# SCK_URBAN_BOARD_2_2.net
KiCad netlist of a schematic drawn in EAGLE
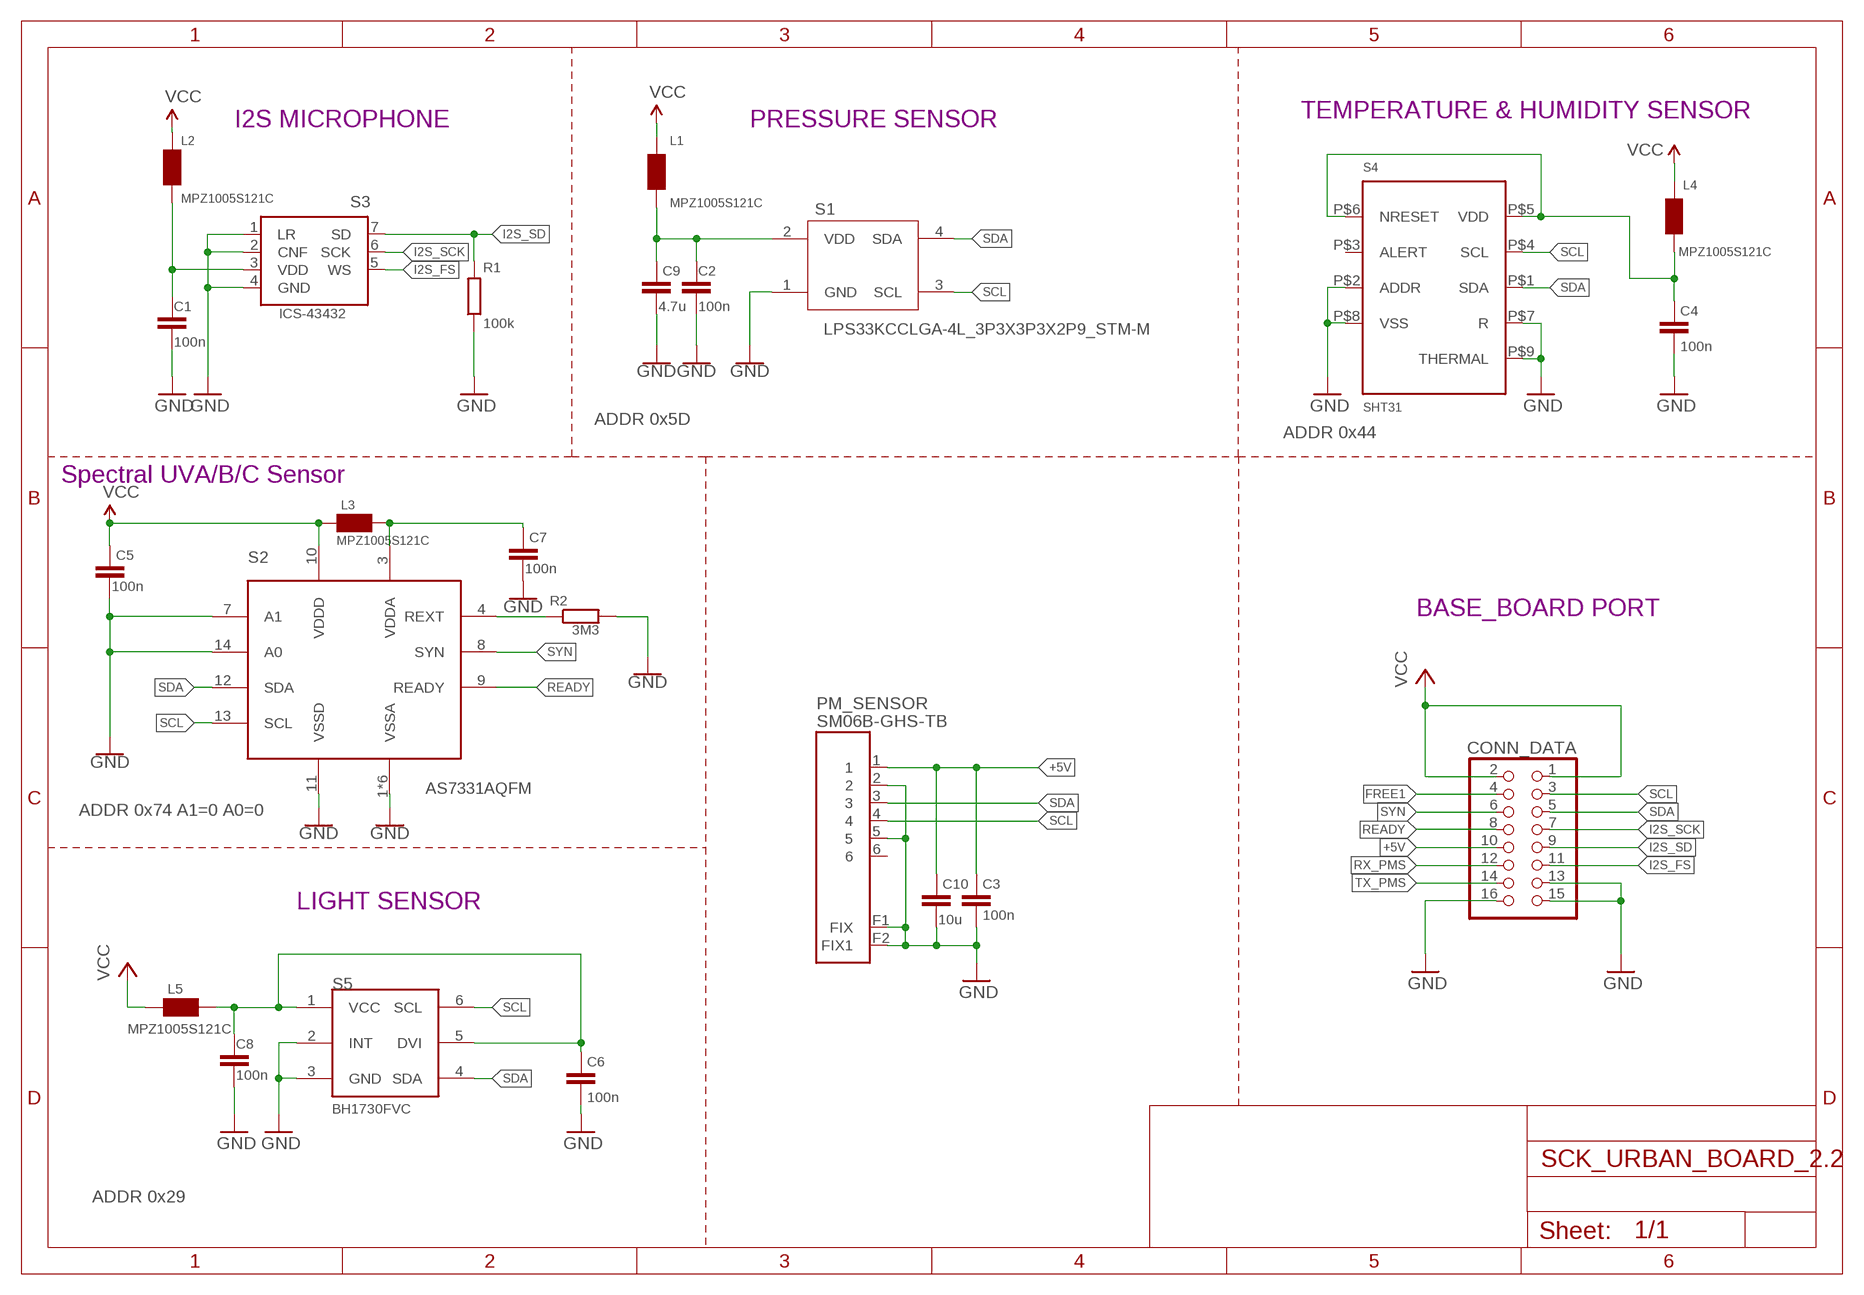
[diagram p0: schematic, sheet 1]

(export (version "E")
  (design (tool "Eeschema 10.0.6"))
  (components
    (comp (ref "C1")
      (value "100n")
      (footprint "eagle-import:C0402")
      (libsource (lib "eagle-import") (part "C-EUC0402"))
    )
    (comp (ref "C2")
      (value "100n")
      (footprint "eagle-import:C0402")
      (libsource (lib "eagle-import") (part "C-EUC0402"))
    )
    (comp (ref "C3")
      (value "100n")
      (footprint "eagle-import:C0402")
      (libsource (lib "eagle-import") (part "C-EUC0402"))
    )
    (comp (ref "C4")
      (value "100n")
      (footprint "eagle-import:C0402")
      (libsource (lib "eagle-import") (part "C-EUC0402"))
    )
    (comp (ref "C5")
      (value "100n")
      (footprint "eagle-import:C0402")
      (libsource (lib "eagle-import") (part "C-EUC0402"))
    )
    (comp (ref "C6")
      (value "100n")
      (footprint "eagle-import:C0402")
      (libsource (lib "eagle-import") (part "C-EUC0402"))
    )
    (comp (ref "C7")
      (value "100n")
      (footprint "eagle-import:C0402")
      (libsource (lib "eagle-import") (part "C-EUC0402"))
    )
    (comp (ref "C8")
      (value "100n")
      (footprint "eagle-import:C0402")
      (libsource (lib "eagle-import") (part "C-EUC0402"))
    )
    (comp (ref "C9")
      (value "4.7u")
      (footprint "eagle-import:C0603")
      (libsource (lib "eagle-import") (part "C-EUC0603"))
    )
    (comp (ref "C10")
      (value "10u")
      (footprint "eagle-import:C0603")
      (libsource (lib "eagle-import") (part "C-EUC0603"))
    )
    (comp (ref "CONN_DATA")
      (value "PINHD_2X8MAL_SMD")
      (footprint "eagle-import:PINHD_2X8_SMD_MALE_UNHOLED")
      (libsource (lib "eagle-import") (part "PINHD_2X8MAL_SMD"))
    )
    (comp (ref "L1")
      (value "MPZ1005S121C")
      (footprint "eagle-import:L0402")
      (libsource (lib "eagle-import") (part "FERRITE-BEAD_0402"))
    )
    (comp (ref "L2")
      (value "MPZ1005S121C")
      (footprint "eagle-import:L0402")
      (libsource (lib "eagle-import") (part "FERRITE-BEAD_0402"))
    )
    (comp (ref "L3")
      (value "MPZ1005S121C")
      (footprint "eagle-import:L0402")
      (libsource (lib "eagle-import") (part "FERRITE-BEAD_0402"))
    )
    (comp (ref "L4")
      (value "MPZ1005S121C")
      (footprint "eagle-import:L0402")
      (libsource (lib "eagle-import") (part "FERRITE-BEAD_0402"))
    )
    (comp (ref "L5")
      (value "MPZ1005S121C")
      (footprint "eagle-import:L0402")
      (libsource (lib "eagle-import") (part "FERRITE-BEAD_0402"))
    )
    (comp (ref "PM_SENSOR")
      (value "SM06B-GHS-TB")
      (footprint "eagle-import:SM06B-GHS-TB")
      (libsource (lib "eagle-import") (part "SM06B-GHS-TB"))
    )
    (comp (ref "R1")
      (value "100k")
      (footprint "eagle-import:R0402")
      (libsource (lib "eagle-import") (part "R-EU_R0402"))
    )
    (comp (ref "R2")
      (value "3M3")
      (footprint "eagle-import:R0402")
      (libsource (lib "eagle-import") (part "R-EU_R0402"))
    )
    (comp (ref "S1")
      (value "LPS33KCCLGA-4L_3P3X3P3X2P9_STM-M")
      (footprint "eagle-import:CCLGA-4L_3P3X3P3X2P9_STM-M")
      (fields
        (field (name "MANUFACTURER_PART_NUMBER") "LPS33K")
        (field (name "COPYRIGHT") "Copyright (C) 2023 Ultra Librarian. All rights reserved.")
      )
      (libsource (lib "eagle-import") (part "LPS33KCCLGA-4L_3P3X3P3X2P9_STM-M"))
    )
    (comp (ref "S2")
      (value "AS7331AQFM")
      (footprint "eagle-import:OLGA16")
      (libsource (lib "eagle-import") (part "AS7331AQFM"))
    )
    (comp (ref "S3")
      (value "ICS-43432")
      (footprint "eagle-import:ICS-43432")
      (libsource (lib "eagle-import") (part "ICS-43432"))
    )
    (comp (ref "S4")
      (value "SHT31")
      (footprint "eagle-import:DFN8_STH3X-DIS")
      (libsource (lib "eagle-import") (part "SHT3X-DIS"))
    )
    (comp (ref "S5")
      (value "BH1730FVC")
      (footprint "eagle-import:WSOF6")
      (libsource (lib "eagle-import") (part "BH1730FVC"))
    )
  )
  (nets
    (net (code "1") (name "+5V") (class "Default")
      (node (ref "C10") (pin "2") (pinfunction "2_2") (pintype "passive"))
      (node (ref "C3") (pin "2") (pinfunction "2_2") (pintype "passive"))
      (node (ref "CONN_DATA") (pin "10") (pinfunction "10_10") (pintype "passive"))
      (node (ref "PM_SENSOR") (pin "1") (pinfunction "1_1") (pintype "bidirectional"))
    )
    (net (code "2") (name "FREE1") (class "Default")
      (node (ref "CONN_DATA") (pin "4") (pinfunction "4_4") (pintype "passive"))
    )
    (net (code "3") (name "GND") (class "Default")
      (node (ref "C1") (pin "1") (pinfunction "1_1") (pintype "passive"))
      (node (ref "C10") (pin "1") (pinfunction "1_1") (pintype "passive"))
      (node (ref "C2") (pin "1") (pinfunction "1_1") (pintype "passive"))
      (node (ref "C3") (pin "1") (pinfunction "1_1") (pintype "passive"))
      (node (ref "C4") (pin "1") (pinfunction "1_1") (pintype "passive"))
      (node (ref "C5") (pin "1") (pinfunction "1_1") (pintype "passive"))
      (node (ref "C6") (pin "1") (pinfunction "1_1") (pintype "passive"))
      (node (ref "C7") (pin "1") (pinfunction "1_1") (pintype "passive"))
      (node (ref "C8") (pin "1") (pinfunction "1_1") (pintype "passive"))
      (node (ref "C9") (pin "1") (pinfunction "1_1") (pintype "passive"))
      (node (ref "CONN_DATA") (pin "13") (pinfunction "13_13") (pintype "passive"))
      (node (ref "CONN_DATA") (pin "15") (pinfunction "15_15") (pintype "passive"))
      (node (ref "CONN_DATA") (pin "16") (pinfunction "16_16") (pintype "passive"))
      (node (ref "PM_SENSOR") (pin "2") (pinfunction "2_2") (pintype "bidirectional"))
      (node (ref "PM_SENSOR") (pin "5") (pinfunction "5_5") (pintype "bidirectional"))
      (node (ref "PM_SENSOR") (pin "F1") (pinfunction "FIX_F1") (pintype "bidirectional"))
      (node (ref "PM_SENSOR") (pin "F2") (pinfunction "FIX1_F2") (pintype "bidirectional"))
      (node (ref "R1") (pin "1") (pinfunction "1_1") (pintype "passive"))
      (node (ref "R2") (pin "2") (pinfunction "2_2") (pintype "passive"))
      (node (ref "S1") (pin "1") (pinfunction "GND_1") (pintype "passive"))
      (node (ref "S2") (pin "1") (pinfunction "VSSA_1") (pintype "bidirectional"))
      (node (ref "S2") (pin "11") (pinfunction "VSSD_11") (pintype "bidirectional"))
      (node (ref "S2") (pin "14") (pinfunction "A0_14") (pintype "bidirectional"))
      (node (ref "S2") (pin "15") (pinfunction "VSSA_15") (pintype "bidirectional"))
      (node (ref "S2") (pin "16") (pinfunction "VSSA_16") (pintype "bidirectional"))
      (node (ref "S2") (pin "2") (pinfunction "VSSA_2") (pintype "bidirectional"))
      (node (ref "S2") (pin "5") (pinfunction "VSSA_5") (pintype "bidirectional"))
      (node (ref "S2") (pin "6") (pinfunction "VSSA_6") (pintype "bidirectional"))
      (node (ref "S2") (pin "7") (pinfunction "A1_7") (pintype "bidirectional"))
      (node (ref "S3") (pin "1") (pinfunction "LR_1") (pintype "bidirectional"))
      (node (ref "S3") (pin "2") (pinfunction "CNF_2") (pintype "bidirectional"))
      (node (ref "S3") (pin "4") (pinfunction "GND_4") (pintype "bidirectional"))
      (node (ref "S4") (pin "P$2") (pinfunction "ADDR_P$2") (pintype "bidirectional"))
      (node (ref "S4") (pin "P$7") (pinfunction "R_P$7") (pintype "bidirectional"))
      (node (ref "S4") (pin "P$8") (pinfunction "VSS_P$8") (pintype "bidirectional"))
      (node (ref "S4") (pin "P$9") (pinfunction "THERMAL_P$9") (pintype "bidirectional"))
      (node (ref "S5") (pin "2") (pinfunction "INT_2") (pintype "bidirectional"))
      (node (ref "S5") (pin "3") (pinfunction "GND_3") (pintype "bidirectional"))
    )
    (net (code "4") (name "I2S_FS") (class "Default")
      (node (ref "CONN_DATA") (pin "11") (pinfunction "11_11") (pintype "passive"))
      (node (ref "S3") (pin "5") (pinfunction "WS_5") (pintype "bidirectional"))
    )
    (net (code "5") (name "I2S_SCK") (class "Default")
      (node (ref "CONN_DATA") (pin "7") (pinfunction "7_7") (pintype "passive"))
      (node (ref "S3") (pin "6") (pinfunction "SCK_6") (pintype "bidirectional"))
    )
    (net (code "6") (name "I2S_SD") (class "Default")
      (node (ref "CONN_DATA") (pin "9") (pinfunction "9_9") (pintype "passive"))
      (node (ref "R1") (pin "2") (pinfunction "2_2") (pintype "passive"))
      (node (ref "S3") (pin "7") (pinfunction "SD_7") (pintype "bidirectional"))
    )
    (net (code "7") (name "Net-(S1-VDD)") (class "Default")
      (node (ref "C2") (pin "2") (pinfunction "2_2") (pintype "passive"))
      (node (ref "C9") (pin "2") (pinfunction "2_2") (pintype "passive"))
      (node (ref "L1") (pin "2") (pinfunction "2_2") (pintype "passive"))
      (node (ref "S1") (pin "2") (pinfunction "VDD_2") (pintype "power_in"))
    )
    (net (code "8") (name "Net-(S2-REXT)") (class "Default")
      (node (ref "R2") (pin "1") (pinfunction "1_1") (pintype "passive"))
      (node (ref "S2") (pin "4") (pinfunction "REXT_4") (pintype "bidirectional"))
    )
    (net (code "9") (name "Net-(S2-VDDA)") (class "Default")
      (node (ref "C7") (pin "2") (pinfunction "2_2") (pintype "passive"))
      (node (ref "L3") (pin "1") (pinfunction "1_1") (pintype "passive"))
      (node (ref "S2") (pin "3") (pinfunction "VDDA_3") (pintype "bidirectional"))
    )
    (net (code "10") (name "Net-(S3-VDD)") (class "Default")
      (node (ref "C1") (pin "2") (pinfunction "2_2") (pintype "passive"))
      (node (ref "L2") (pin "2") (pinfunction "2_2") (pintype "passive"))
      (node (ref "S3") (pin "3") (pinfunction "VDD_3") (pintype "bidirectional"))
    )
    (net (code "11") (name "Net-(S4-NRESET)") (class "Default")
      (node (ref "C4") (pin "2") (pinfunction "2_2") (pintype "passive"))
      (node (ref "L4") (pin "2") (pinfunction "2_2") (pintype "passive"))
      (node (ref "S4") (pin "P$5") (pinfunction "VDD_P$5") (pintype "bidirectional"))
      (node (ref "S4") (pin "P$6") (pinfunction "NRESET_P$6") (pintype "bidirectional"))
    )
    (net (code "12") (name "Net-(S5-DVI)") (class "Default")
      (node (ref "C6") (pin "2") (pinfunction "2_2") (pintype "passive"))
      (node (ref "C8") (pin "2") (pinfunction "2_2") (pintype "passive"))
      (node (ref "L5") (pin "2") (pinfunction "2_2") (pintype "passive"))
      (node (ref "S5") (pin "1") (pinfunction "VCC_1") (pintype "bidirectional"))
      (node (ref "S5") (pin "5") (pinfunction "DVI_5") (pintype "bidirectional"))
    )
    (net (code "13") (name "READY") (class "Default")
      (node (ref "CONN_DATA") (pin "8") (pinfunction "8_8") (pintype "passive"))
      (node (ref "S2") (pin "9") (pinfunction "READY_9") (pintype "bidirectional"))
    )
    (net (code "14") (name "RX_PMS") (class "Default")
      (node (ref "CONN_DATA") (pin "12") (pinfunction "12_12") (pintype "passive"))
    )
    (net (code "15") (name "SCL") (class "Default")
      (node (ref "CONN_DATA") (pin "3") (pinfunction "3_3") (pintype "passive"))
      (node (ref "PM_SENSOR") (pin "4") (pinfunction "4_4") (pintype "bidirectional"))
      (node (ref "S1") (pin "3") (pinfunction "SCL_3") (pintype "input"))
      (node (ref "S2") (pin "13") (pinfunction "SCL_13") (pintype "bidirectional"))
      (node (ref "S4") (pin "P$4") (pinfunction "SCL_P$4") (pintype "bidirectional"))
      (node (ref "S5") (pin "6") (pinfunction "SCL_6") (pintype "bidirectional"))
    )
    (net (code "16") (name "SDA") (class "Default")
      (node (ref "CONN_DATA") (pin "5") (pinfunction "5_5") (pintype "passive"))
      (node (ref "PM_SENSOR") (pin "3") (pinfunction "3_3") (pintype "bidirectional"))
      (node (ref "S1") (pin "4") (pinfunction "SDA_4") (pintype "bidirectional"))
      (node (ref "S2") (pin "12") (pinfunction "SDA_12") (pintype "bidirectional"))
      (node (ref "S4") (pin "P$1") (pinfunction "SDA_P$1") (pintype "bidirectional"))
      (node (ref "S5") (pin "4") (pinfunction "SDA_4") (pintype "bidirectional"))
    )
    (net (code "17") (name "SYN") (class "Default")
      (node (ref "CONN_DATA") (pin "6") (pinfunction "6_6") (pintype "passive"))
      (node (ref "S2") (pin "8") (pinfunction "SYN_8") (pintype "bidirectional"))
    )
    (net (code "18") (name "TX_PMS") (class "Default")
      (node (ref "CONN_DATA") (pin "14") (pinfunction "14_14") (pintype "passive"))
    )
    (net (code "19") (name "VCC") (class "Default")
      (node (ref "C5") (pin "2") (pinfunction "2_2") (pintype "passive"))
      (node (ref "CONN_DATA") (pin "1") (pinfunction "1_1") (pintype "passive"))
      (node (ref "CONN_DATA") (pin "2") (pinfunction "2_2") (pintype "passive"))
      (node (ref "L1") (pin "1") (pinfunction "1_1") (pintype "passive"))
      (node (ref "L2") (pin "1") (pinfunction "1_1") (pintype "passive"))
      (node (ref "L3") (pin "2") (pinfunction "2_2") (pintype "passive"))
      (node (ref "L4") (pin "1") (pinfunction "1_1") (pintype "passive"))
      (node (ref "L5") (pin "1") (pinfunction "1_1") (pintype "passive"))
      (node (ref "S2") (pin "10") (pinfunction "VDDD_10") (pintype "bidirectional"))
    )
    (net (code "20") (name "unconnected-(PM_SENSOR-Pad6)") (class "Default")
      (node (ref "PM_SENSOR") (pin "6") (pinfunction "6_6") (pintype "bidirectional"))
    )
    (net (code "21") (name "unconnected-(S4-ALERT-PadP$3)") (class "Default")
      (node (ref "S4") (pin "P$3") (pinfunction "ALERT_P$3") (pintype "bidirectional"))
    )
  )
)
